# Mixer-Analog-OPA2134-Rev-H.net
KiCad netlist of a schematic drawn in EAGLE
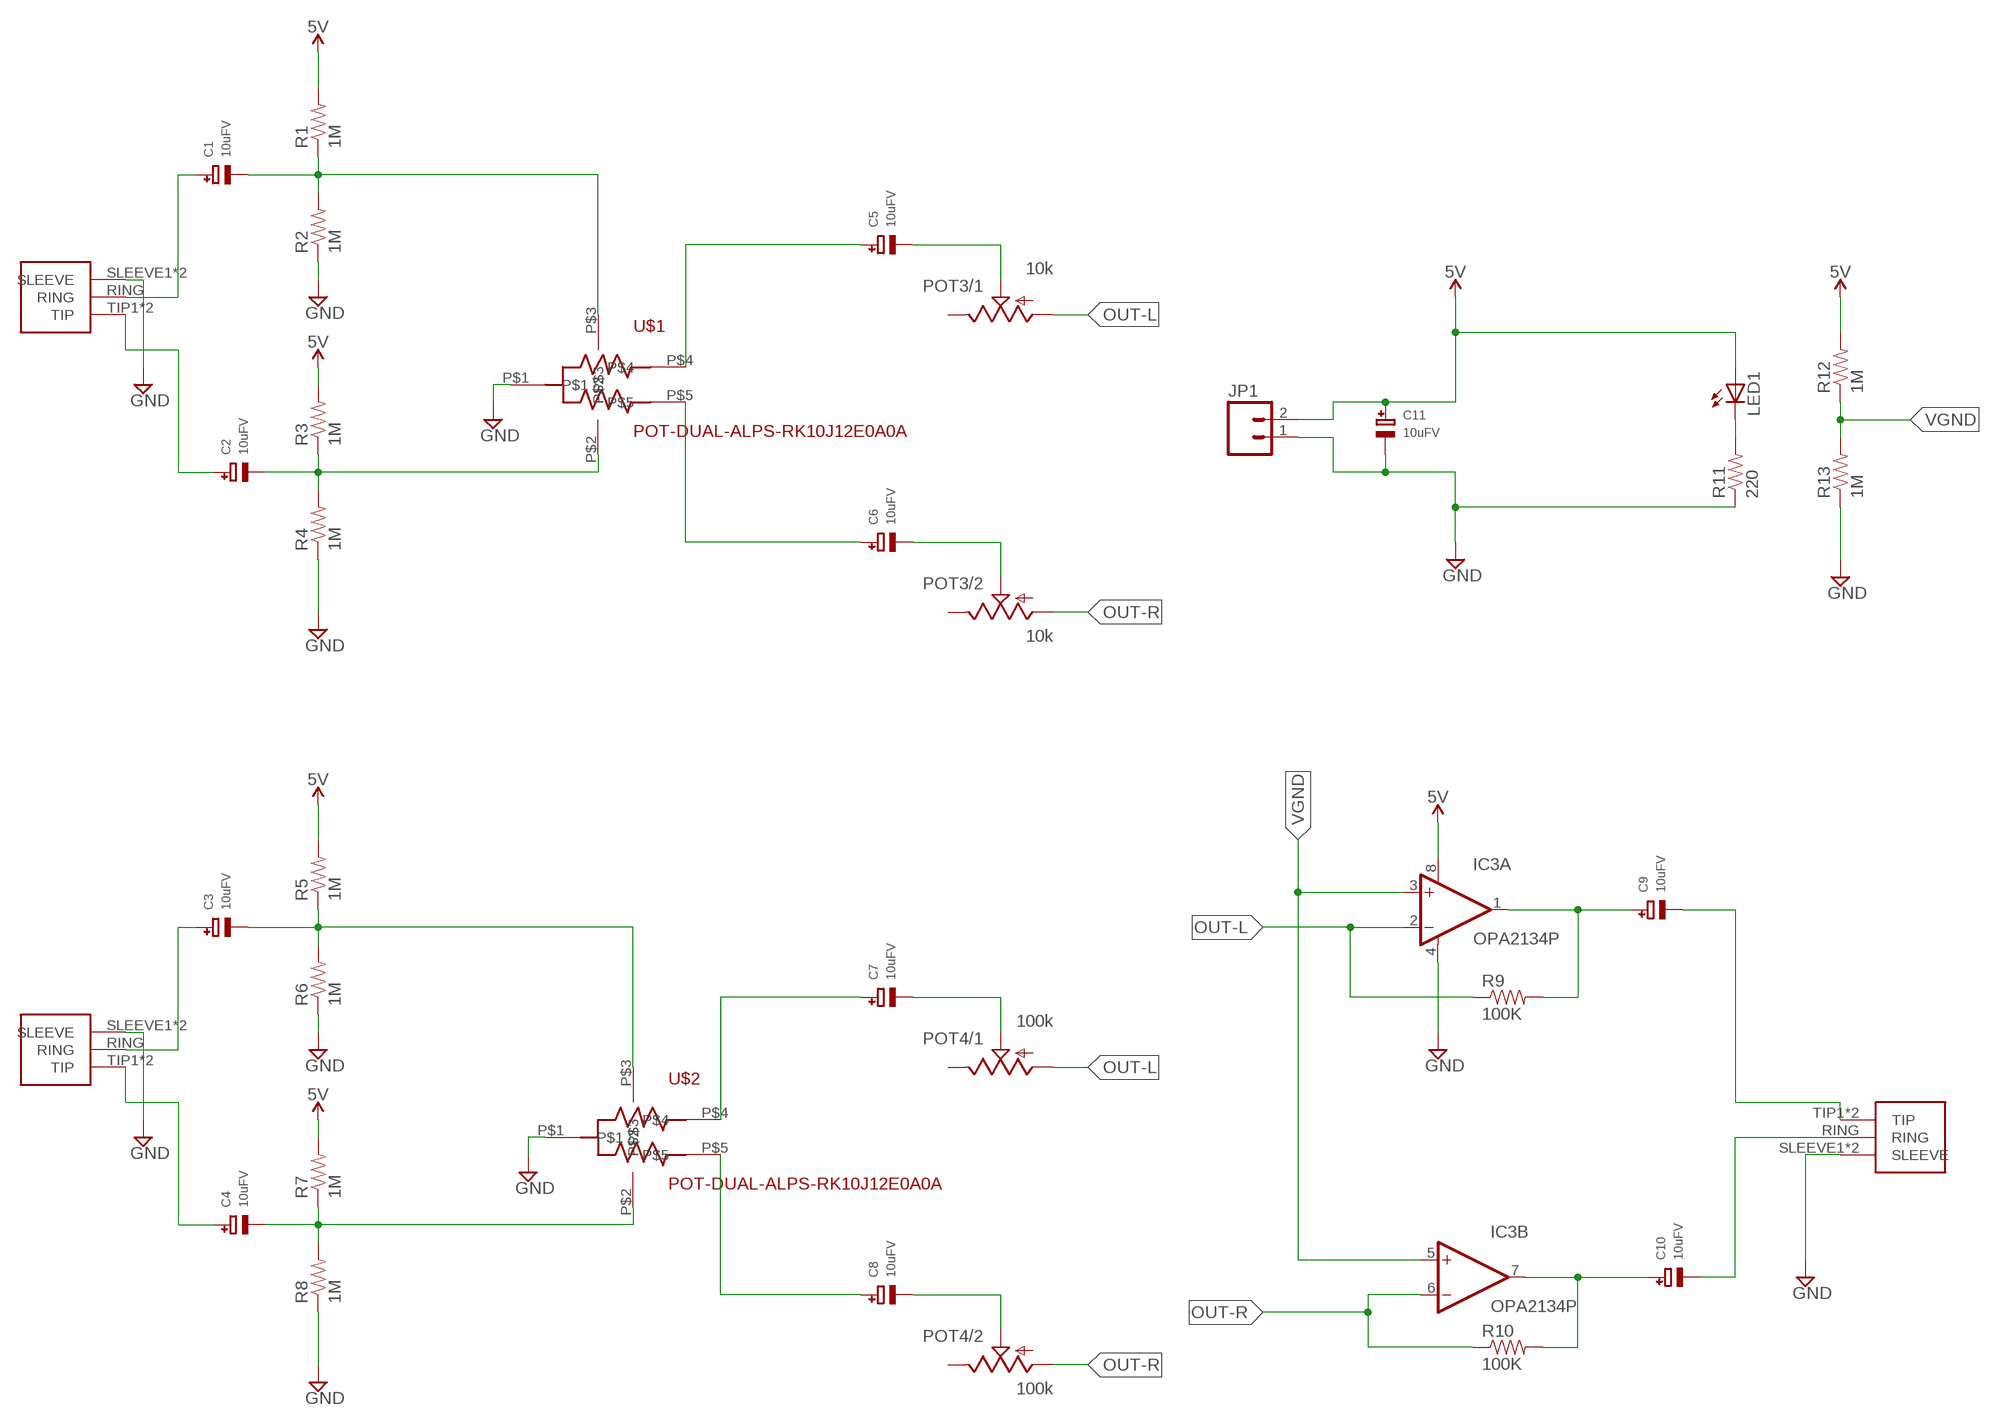
[diagram p0: schematic, sheet 1]

(export (version "E")
  (design (tool "Eeschema 10.0.6"))
  (components
    (comp (ref "C1")
      (value "10uFV")
      (footprint "eagle-import:CELEC_3.5MM_8MM")
      (libsource (lib "eagle-import") (part "CAP_ELECTROLYTICPTH_3.5MMGRID_8MMDIA"))
    )
    (comp (ref "C2")
      (value "10uFV")
      (footprint "eagle-import:CELEC_3.5MM_8MM")
      (libsource (lib "eagle-import") (part "CAP_ELECTROLYTICPTH_3.5MMGRID_8MMDIA"))
    )
    (comp (ref "C3")
      (value "10uFV")
      (footprint "eagle-import:CELEC_3.5MM_8MM")
      (libsource (lib "eagle-import") (part "CAP_ELECTROLYTICPTH_3.5MMGRID_8MMDIA"))
    )
    (comp (ref "C4")
      (value "10uFV")
      (footprint "eagle-import:CELEC_3.5MM_8MM")
      (libsource (lib "eagle-import") (part "CAP_ELECTROLYTICPTH_3.5MMGRID_8MMDIA"))
    )
    (comp (ref "C5")
      (value "10uFV")
      (footprint "eagle-import:CELEC_3.5MM_8MM")
      (libsource (lib "eagle-import") (part "CAP_ELECTROLYTICPTH_3.5MMGRID_8MMDIA"))
    )
    (comp (ref "C6")
      (value "10uFV")
      (footprint "eagle-import:CELEC_3.5MM_8MM")
      (libsource (lib "eagle-import") (part "CAP_ELECTROLYTICPTH_3.5MMGRID_8MMDIA"))
    )
    (comp (ref "C7")
      (value "10uFV")
      (footprint "eagle-import:CELEC_3.5MM_8MM")
      (libsource (lib "eagle-import") (part "CAP_ELECTROLYTICPTH_3.5MMGRID_8MMDIA"))
    )
    (comp (ref "C8")
      (value "10uFV")
      (footprint "eagle-import:CELEC_3.5MM_8MM")
      (libsource (lib "eagle-import") (part "CAP_ELECTROLYTICPTH_3.5MMGRID_8MMDIA"))
    )
    (comp (ref "C9")
      (value "10uFV")
      (footprint "eagle-import:CELEC_3.5MM_8MM")
      (libsource (lib "eagle-import") (part "CAP_ELECTROLYTICPTH_3.5MMGRID_8MMDIA"))
    )
    (comp (ref "C10")
      (value "10uFV")
      (footprint "eagle-import:CELEC_3.5MM_8MM")
      (libsource (lib "eagle-import") (part "CAP_ELECTROLYTICPTH_3.5MMGRID_8MMDIA"))
    )
    (comp (ref "C11")
      (value "10uFV")
      (footprint "eagle-import:CELEC_3.5MM_8MM")
      (libsource (lib "eagle-import") (part "CAP_ELECTROLYTICPTH_3.5MMGRID_8MMDIA"))
    )
    (comp (ref "IC3")
      (value "OPA2134P")
      (footprint "eagle-import:DIL08")
      (fields (field (name "MF") "TEXAS INSTRUMENTS") (field (name "MPN") "OPA2134PA"))
      (libsource (lib "eagle-import") (part "OPA2134P"))
    )
    (comp (ref "J1")
      (value "1/8\"-F-STEREO-PCB")
      (footprint "eagle-import:1_8_-F-STEREO-PCB")
      (libsource (lib "eagle-import") (part "1/8{dblquote}-F-STEREO-PCB"))
    )
    (comp (ref "J2")
      (value "1/8\"-F-STEREO-PCB")
      (footprint "eagle-import:1_8_-F-STEREO-PCB")
      (libsource (lib "eagle-import") (part "1/8{dblquote}-F-STEREO-PCB"))
    )
    (comp (ref "J3")
      (value "1/8\"-F-STEREO-PCB")
      (footprint "eagle-import:1_8_-F-STEREO-PCB")
      (libsource (lib "eagle-import") (part "1/8{dblquote}-F-STEREO-PCB"))
    )
    (comp (ref "JP1")
      (value "M02LOCK")
      (footprint "eagle-import:1X02_LOCK")
      (libsource (lib "eagle-import") (part "M02LOCK"))
    )
    (comp (ref "LED1")
      (value "LED3MM")
      (footprint "eagle-import:LED3MM")
      (libsource (lib "eagle-import") (part "LED3MM"))
    )
    (comp (ref "POT3")
      (value "10k")
      (footprint "eagle-import:PTV112")
      (fields
        (field (name "MF") "STMicroelectronics")
        (field (name "MP") "PTV112")
        (field (name "SPICEPREFIX") "J")
      )
      (libsource (lib "eagle-import") (part "POT-DUAL-PTV112-4420"))
    )
    (comp (ref "POT4")
      (value "100k")
      (footprint "eagle-import:PTV112")
      (fields
        (field (name "MF") "STMicroelectronics")
        (field (name "MP") "PTV112")
        (field (name "SPICEPREFIX") "J")
      )
      (libsource (lib "eagle-import") (part "POT-DUAL-PTV112-4420"))
    )
    (comp (ref "R1")
      (value "1M")
      (footprint "eagle-import:AXIAL-0.3EZ")
      (fields (field (name "SPICEPREFIX") "R"))
      (libsource (lib "eagle-import") (part "RESISTOREZ"))
    )
    (comp (ref "R2")
      (value "1M")
      (footprint "eagle-import:AXIAL-0.3")
      (fields (field (name "SPICEPREFIX") "R"))
      (libsource (lib "eagle-import") (part "RESISTORAXIAL-0.3"))
    )
    (comp (ref "R3")
      (value "1M")
      (footprint "eagle-import:AXIAL-0.3EZ")
      (fields (field (name "SPICEPREFIX") "R"))
      (libsource (lib "eagle-import") (part "RESISTOREZ"))
    )
    (comp (ref "R4")
      (value "1M")
      (footprint "eagle-import:AXIAL-0.3EZ")
      (fields (field (name "SPICEPREFIX") "R"))
      (libsource (lib "eagle-import") (part "RESISTOREZ"))
    )
    (comp (ref "R5")
      (value "1M")
      (footprint "eagle-import:AXIAL-0.3EZ")
      (fields (field (name "SPICEPREFIX") "R"))
      (libsource (lib "eagle-import") (part "RESISTOREZ"))
    )
    (comp (ref "R6")
      (value "1M")
      (footprint "eagle-import:AXIAL-0.3EZ")
      (fields (field (name "SPICEPREFIX") "R"))
      (libsource (lib "eagle-import") (part "RESISTOREZ"))
    )
    (comp (ref "R7")
      (value "1M")
      (footprint "eagle-import:AXIAL-0.3EZ")
      (fields (field (name "SPICEPREFIX") "R"))
      (libsource (lib "eagle-import") (part "RESISTOREZ"))
    )
    (comp (ref "R8")
      (value "1M")
      (footprint "eagle-import:AXIAL-0.3EZ")
      (fields (field (name "SPICEPREFIX") "R"))
      (libsource (lib "eagle-import") (part "RESISTOREZ"))
    )
    (comp (ref "R9")
      (value "100K")
      (footprint "eagle-import:AXIAL-0.3EZ")
      (fields (field (name "SPICEPREFIX") "R"))
      (libsource (lib "eagle-import") (part "RESISTOREZ"))
    )
    (comp (ref "R10")
      (value "100K")
      (footprint "eagle-import:AXIAL-0.3EZ")
      (fields (field (name "SPICEPREFIX") "R"))
      (libsource (lib "eagle-import") (part "RESISTOREZ"))
    )
    (comp (ref "R11")
      (value "220")
      (footprint "eagle-import:AXIAL-0.3EZ")
      (libsource (lib "eagle-import") (part "RESISTOREZ"))
    )
    (comp (ref "R12")
      (value "1M")
      (footprint "eagle-import:AXIAL-0.3EZ")
      (libsource (lib "eagle-import") (part "RESISTOREZ"))
    )
    (comp (ref "R13")
      (value "1M")
      (footprint "eagle-import:AXIAL-0.3EZ")
      (libsource (lib "eagle-import") (part "RESISTOREZ"))
    )
    (comp (ref "U$1")
      (value "POT-DUAL-ALPS-RK10J12E0A0A")
      (footprint "eagle-import:POT-DUAL-ALPS-RK10J12E0A0A")
      (libsource (lib "eagle-import") (part "POT-DUAL-ALPS-RK10J12E0A0A"))
    )
    (comp (ref "U$2")
      (value "POT-DUAL-ALPS-RK10J12E0A0A")
      (footprint "eagle-import:POT-DUAL-ALPS-RK10J12E0A0A")
      (libsource (lib "eagle-import") (part "POT-DUAL-ALPS-RK10J12E0A0A"))
    )
  )
  (nets
    (net (code "1") (name "5V") (class "Default")
      (node (ref "C11") (pin "+") (pinfunction "+_+") (pintype "passive"))
      (node (ref "IC3") (pin "8") (pinfunction "V+_8") (pintype "power_in"))
      (node (ref "JP1") (pin "2") (pinfunction "2_2") (pintype "passive"))
      (node (ref "LED1") (pin "A") (pinfunction "A_A") (pintype "passive"))
      (node (ref "R1") (pin "P$2") (pinfunction "2_P$2") (pintype "passive"))
      (node (ref "R12") (pin "P$2") (pinfunction "2_P$2") (pintype "passive"))
      (node (ref "R3") (pin "P$2") (pinfunction "2_P$2") (pintype "passive"))
      (node (ref "R5") (pin "P$2") (pinfunction "2_P$2") (pintype "passive"))
      (node (ref "R7") (pin "P$2") (pinfunction "2_P$2") (pintype "passive"))
    )
    (net (code "2") (name "GND") (class "Default")
      (node (ref "C11") (pin "-") (pinfunction "-_-") (pintype "passive"))
      (node (ref "IC3") (pin "4") (pinfunction "V-_4") (pintype "power_in"))
      (node (ref "J1") (pin "SLEEVE1") (pinfunction "SLEEVE_SLEEVE1") (pintype "bidirectional"))
      (node (ref "J1") (pin "SLEEVE2") (pinfunction "SLEEVE_SLEEVE2") (pintype "bidirectional"))
      (node (ref "J2") (pin "SLEEVE1") (pinfunction "SLEEVE_SLEEVE1") (pintype "bidirectional"))
      (node (ref "J2") (pin "SLEEVE2") (pinfunction "SLEEVE_SLEEVE2") (pintype "bidirectional"))
      (node (ref "J3") (pin "SLEEVE1") (pinfunction "SLEEVE_SLEEVE1") (pintype "bidirectional"))
      (node (ref "J3") (pin "SLEEVE2") (pinfunction "SLEEVE_SLEEVE2") (pintype "bidirectional"))
      (node (ref "JP1") (pin "1") (pinfunction "1_1") (pintype "passive"))
      (node (ref "R11") (pin "P$1") (pinfunction "1_P$1") (pintype "passive"))
      (node (ref "R13") (pin "P$1") (pinfunction "1_P$1") (pintype "passive"))
      (node (ref "R2") (pin "P$1") (pinfunction "1_P$1") (pintype "passive"))
      (node (ref "R4") (pin "P$1") (pinfunction "1_P$1") (pintype "passive"))
      (node (ref "R6") (pin "P$1") (pinfunction "1_P$1") (pintype "passive"))
      (node (ref "R8") (pin "P$1") (pinfunction "1_P$1") (pintype "passive"))
      (node (ref "U$1") (pin "P$1") (pinfunction "P$1_P$1") (pintype "bidirectional"))
      (node (ref "U$2") (pin "P$1") (pinfunction "P$1_P$1") (pintype "bidirectional"))
    )
    (net (code "3") (name "Net-(C1-Pad+)") (class "Default")
      (node (ref "C1") (pin "+") (pinfunction "+_+") (pintype "passive"))
      (node (ref "J1") (pin "RING") (pinfunction "RING_RING") (pintype "bidirectional"))
    )
    (net (code "4") (name "Net-(C2-Pad+)") (class "Default")
      (node (ref "C2") (pin "+") (pinfunction "+_+") (pintype "passive"))
      (node (ref "J1") (pin "TIP1") (pinfunction "TIP_TIP1") (pintype "bidirectional"))
      (node (ref "J1") (pin "TIP2") (pinfunction "TIP_TIP2") (pintype "bidirectional"))
    )
    (net (code "5") (name "Net-(C3-Pad+)") (class "Default")
      (node (ref "C3") (pin "+") (pinfunction "+_+") (pintype "passive"))
      (node (ref "J2") (pin "RING") (pinfunction "RING_RING") (pintype "bidirectional"))
    )
    (net (code "6") (name "Net-(C4-Pad+)") (class "Default")
      (node (ref "C4") (pin "+") (pinfunction "+_+") (pintype "passive"))
      (node (ref "J2") (pin "TIP1") (pinfunction "TIP_TIP1") (pintype "bidirectional"))
      (node (ref "J2") (pin "TIP2") (pinfunction "TIP_TIP2") (pintype "bidirectional"))
    )
    (net (code "7") (name "Net-(C5-Pad+)") (class "Default")
      (node (ref "C5") (pin "+") (pinfunction "+_+") (pintype "passive"))
      (node (ref "U$1") (pin "P$4") (pinfunction "P$4_P$4") (pintype "bidirectional"))
    )
    (net (code "8") (name "Net-(C6-Pad+)") (class "Default")
      (node (ref "C6") (pin "+") (pinfunction "+_+") (pintype "passive"))
      (node (ref "U$1") (pin "P$5") (pinfunction "P$5_P$5") (pintype "bidirectional"))
    )
    (net (code "9") (name "Net-(C7-Pad+)") (class "Default")
      (node (ref "C7") (pin "+") (pinfunction "+_+") (pintype "passive"))
      (node (ref "U$2") (pin "P$4") (pinfunction "P$4_P$4") (pintype "bidirectional"))
    )
    (net (code "10") (name "Net-(C8-Pad+)") (class "Default")
      (node (ref "C8") (pin "+") (pinfunction "+_+") (pintype "passive"))
      (node (ref "U$2") (pin "P$5") (pinfunction "P$5_P$5") (pintype "bidirectional"))
    )
    (net (code "11") (name "Net-(C9-Pad-)") (class "Default")
      (node (ref "C9") (pin "-") (pinfunction "-_-") (pintype "passive"))
      (node (ref "J3") (pin "TIP1") (pinfunction "TIP_TIP1") (pintype "bidirectional"))
      (node (ref "J3") (pin "TIP2") (pinfunction "TIP_TIP2") (pintype "bidirectional"))
    )
    (net (code "12") (name "Net-(C10-Pad-)") (class "Default")
      (node (ref "C10") (pin "-") (pinfunction "-_-") (pintype "passive"))
      (node (ref "J3") (pin "RING") (pinfunction "RING_RING") (pintype "bidirectional"))
    )
    (net (code "13") (name "Net-(IC3A-OUT)") (class "Default")
      (node (ref "C9") (pin "+") (pinfunction "+_+") (pintype "passive"))
      (node (ref "IC3") (pin "1") (pinfunction "OUT_1") (pintype "output"))
      (node (ref "R9") (pin "P$2") (pinfunction "2_P$2") (pintype "passive"))
    )
    (net (code "14") (name "Net-(IC3B-OUT)") (class "Default")
      (node (ref "C10") (pin "+") (pinfunction "+_+") (pintype "passive"))
      (node (ref "IC3") (pin "7") (pinfunction "OUT_7") (pintype "output"))
      (node (ref "R10") (pin "P$2") (pinfunction "2_P$2") (pintype "passive"))
    )
    (net (code "15") (name "Net-(LED1-C)") (class "Default")
      (node (ref "LED1") (pin "K") (pinfunction "C_K") (pintype "passive"))
      (node (ref "R11") (pin "P$2") (pinfunction "2_P$2") (pintype "passive"))
    )
    (net (code "16") (name "Net-(POT3A-S)") (class "Default")
      (node (ref "C5") (pin "-") (pinfunction "-_-") (pintype "passive"))
      (node (ref "POT3") (pin "1.2") (pinfunction "S_1.2") (pintype "passive"))
    )
    (net (code "17") (name "Net-(POT3B-S)") (class "Default")
      (node (ref "C6") (pin "-") (pinfunction "-_-") (pintype "passive"))
      (node (ref "POT3") (pin "2.2") (pinfunction "S_2.2") (pintype "passive"))
    )
    (net (code "18") (name "Net-(POT4A-S)") (class "Default")
      (node (ref "C7") (pin "-") (pinfunction "-_-") (pintype "passive"))
      (node (ref "POT4") (pin "1.2") (pinfunction "S_1.2") (pintype "passive"))
    )
    (net (code "19") (name "Net-(POT4B-S)") (class "Default")
      (node (ref "C8") (pin "-") (pinfunction "-_-") (pintype "passive"))
      (node (ref "POT4") (pin "2.2") (pinfunction "S_2.2") (pintype "passive"))
    )
    (net (code "20") (name "Net-(R1-1)") (class "Default")
      (node (ref "C1") (pin "-") (pinfunction "-_-") (pintype "passive"))
      (node (ref "R1") (pin "P$1") (pinfunction "1_P$1") (pintype "passive"))
      (node (ref "R2") (pin "P$2") (pinfunction "2_P$2") (pintype "passive"))
      (node (ref "U$1") (pin "P$3") (pinfunction "P$3_P$3") (pintype "bidirectional"))
    )
    (net (code "21") (name "Net-(R3-1)") (class "Default")
      (node (ref "C2") (pin "-") (pinfunction "-_-") (pintype "passive"))
      (node (ref "R3") (pin "P$1") (pinfunction "1_P$1") (pintype "passive"))
      (node (ref "R4") (pin "P$2") (pinfunction "2_P$2") (pintype "passive"))
      (node (ref "U$1") (pin "P$2") (pinfunction "P$2_P$2") (pintype "bidirectional"))
    )
    (net (code "22") (name "Net-(R5-1)") (class "Default")
      (node (ref "C3") (pin "-") (pinfunction "-_-") (pintype "passive"))
      (node (ref "R5") (pin "P$1") (pinfunction "1_P$1") (pintype "passive"))
      (node (ref "R6") (pin "P$2") (pinfunction "2_P$2") (pintype "passive"))
      (node (ref "U$2") (pin "P$3") (pinfunction "P$3_P$3") (pintype "bidirectional"))
    )
    (net (code "23") (name "Net-(R7-1)") (class "Default")
      (node (ref "C4") (pin "-") (pinfunction "-_-") (pintype "passive"))
      (node (ref "R7") (pin "P$1") (pinfunction "1_P$1") (pintype "passive"))
      (node (ref "R8") (pin "P$2") (pinfunction "2_P$2") (pintype "passive"))
      (node (ref "U$2") (pin "P$2") (pinfunction "P$2_P$2") (pintype "bidirectional"))
    )
    (net (code "24") (name "OUT-L") (class "Default")
      (node (ref "IC3") (pin "2") (pinfunction "-IN_2") (pintype "input"))
      (node (ref "POT3") (pin "1.1") (pinfunction "A_1.1") (pintype "passive"))
      (node (ref "POT4") (pin "1.1") (pinfunction "A_1.1") (pintype "passive"))
      (node (ref "R9") (pin "P$1") (pinfunction "1_P$1") (pintype "passive"))
    )
    (net (code "25") (name "OUT-R") (class "Default")
      (node (ref "IC3") (pin "6") (pinfunction "-IN_6") (pintype "input"))
      (node (ref "POT3") (pin "2.1") (pinfunction "A_2.1") (pintype "passive"))
      (node (ref "POT4") (pin "2.1") (pinfunction "A_2.1") (pintype "passive"))
      (node (ref "R10") (pin "P$1") (pinfunction "1_P$1") (pintype "passive"))
    )
    (net (code "26") (name "VGND") (class "Default")
      (node (ref "IC3") (pin "3") (pinfunction "+IN_3") (pintype "input"))
      (node (ref "IC3") (pin "5") (pinfunction "+IN_5") (pintype "input"))
      (node (ref "R12") (pin "P$1") (pinfunction "1_P$1") (pintype "passive"))
      (node (ref "R13") (pin "P$2") (pinfunction "2_P$2") (pintype "passive"))
    )
    (net (code "27") (name "unconnected-(POT3A-E-Pad1.3)") (class "Default")
      (node (ref "POT3") (pin "1.3") (pinfunction "E_1.3") (pintype "passive"))
    )
    (net (code "28") (name "unconnected-(POT3B-E-Pad2.3)") (class "Default")
      (node (ref "POT3") (pin "2.3") (pinfunction "E_2.3") (pintype "passive"))
    )
    (net (code "29") (name "unconnected-(POT4A-E-Pad1.3)") (class "Default")
      (node (ref "POT4") (pin "1.3") (pinfunction "E_1.3") (pintype "passive"))
    )
    (net (code "30") (name "unconnected-(POT4B-E-Pad2.3)") (class "Default")
      (node (ref "POT4") (pin "2.3") (pinfunction "E_2.3") (pintype "passive"))
    )
  )
)
